# Lockbox_Schematic_V1_0.net
KiCad netlist of a schematic drawn in Altium Designer
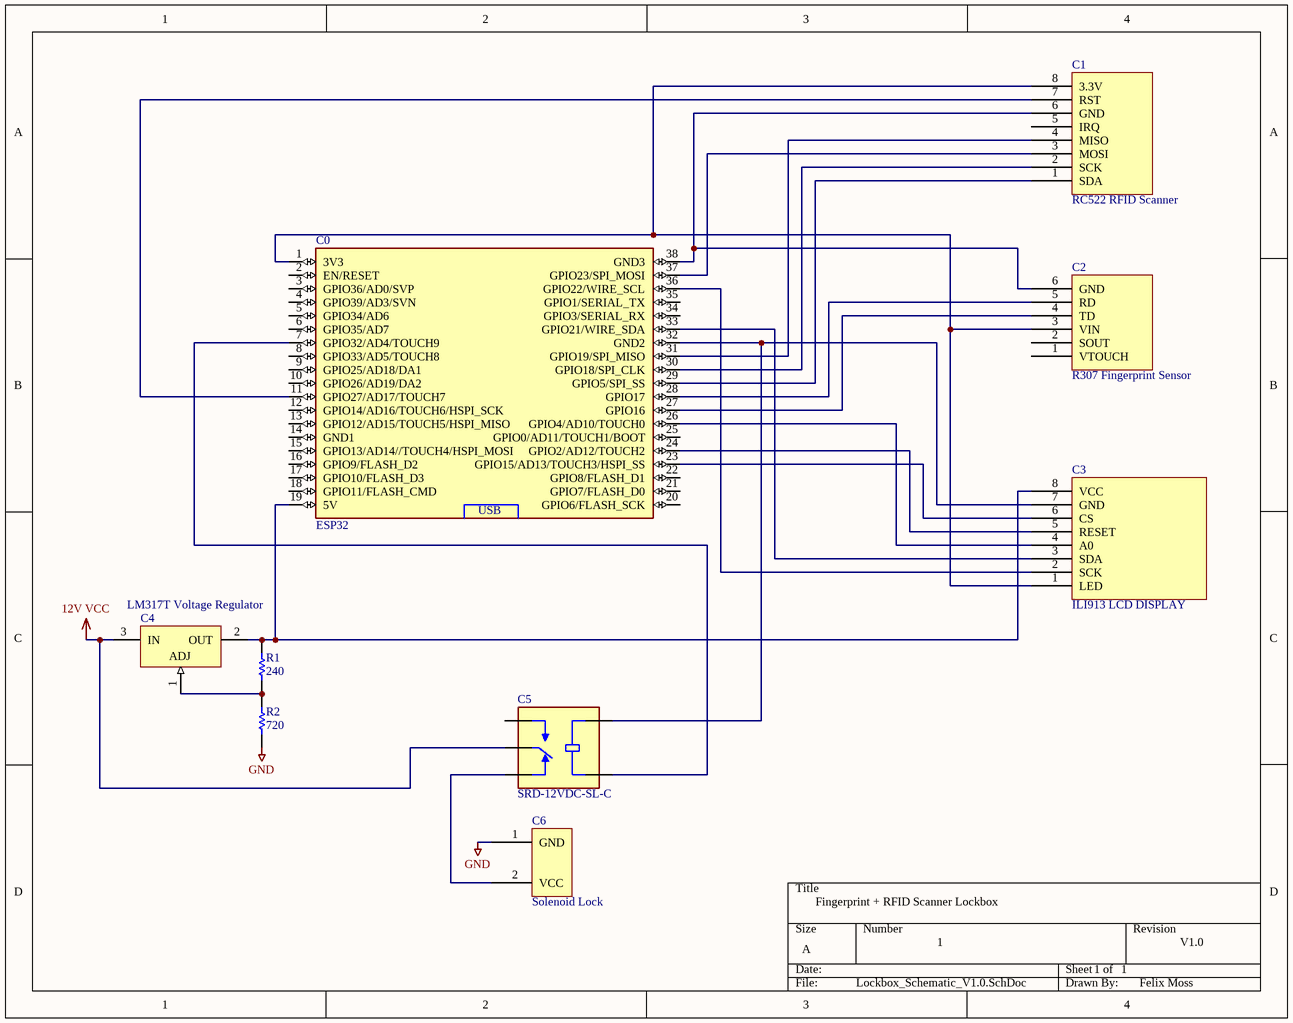
[diagram p0: Lockbox_Schematic_V1.0.SchDoc]

(export (version "E")
  (design (tool "Eeschema 10.0.6"))
  (components
    (comp (ref "C0")
      (value "ESP32")
      (footprint "ESP32-DEVKITC")
      (fields (field (name "MF") "Espressif Systems") (field (name "MP") "ESP32-DevKitC"))
      (libsource (lib "ESP32-DEVKITC") (part "ESP32-DEVKITC"))
    )
    (comp (ref "C1")
      (value "RC522 RFID Scanner")
      (description "RFID Scanner")
      (libsource (lib "Fingerprint_Mechanism_Library") (part "RFID-RC522"))
    )
    (comp (ref "C2")
      (value "R307 Fingerprint Sensor")
      (description "Fingerprint Sensor Powered by AS608")
      (libsource (lib "Fingerprint_Mechanism_Library") (part "Fingerprint Sensor"))
    )
    (comp (ref "C3")
      (value "ILI913 LCD DISPLAY")
      (description "LCD-1217")
      (libsource (lib "Fingerprint_Mechanism_Library") (part "LCD TFT DISPLAY"))
    )
    (comp (ref "C4")
      (value "LM317T Voltage Regulator")
      (footprint "TO-220")
      (description "1.5A, 1.2V to 37V Adjustable Voltage Regulator, 3-Pin TO-220")
      (libsource (lib "Altium Content Vault") (part "PM-REG-117-SIL3"))
    )
    (comp (ref "C5")
      (value "SRD-12VDC-SL-C")
      (footprint "RELAY_SRD-12VDC-SL-C")
      (description "General Purpose Non Latching 12VDC SPDT Through Hole Relays RoHS")
      (libsource (lib "SRD-12VDC-SL-C") (part "SRD-12VDC-SL-C"))
    )
    (comp (ref "C6")
      (value "Solenoid Lock")
      (description "12V 1.1A Solenoid Lock")
      (libsource (lib "Fingerprint_Mechanism_Library") (part "Solenoid Lock"))
    )
    (comp (ref "R1")
      (value "240")
      (description "Resistor")
      (libsource (lib "Simulation Generic Components") (part "Resistor"))
    )
    (comp (ref "R2")
      (value "720")
      (description "Resistor")
      (libsource (lib "Simulation Generic Components") (part "Resistor"))
    )
  )
  (nets
    (net (code "1") (name "12V VCC") (class "Default")
      (node (ref "C4") (pin "3") (pinfunction "IN_3") (pintype "power_in"))
      (node (ref "C5") (pin "COM") (pinfunction "COM_COM") (pintype "passive"))
    )
    (net (code "2") (name "GND") (class "Default")
      (node (ref "C6") (pin "1") (pinfunction "GND_1") (pintype "passive"))
      (node (ref "R2") (pin "1") (pinfunction "1_1") (pintype "passive"))
    )
    (net (code "3") (name "Net-(C0-3V3)") (class "Default")
      (node (ref "C0") (pin "1") (pinfunction "3V3_1") (pintype "bidirectional"))
      (node (ref "C1") (pin "8") (pinfunction "3.3V_8") (pintype "passive"))
      (node (ref "C2") (pin "3") (pinfunction "VIN_3") (pintype "passive"))
      (node (ref "C3") (pin "1") (pinfunction "LED_1") (pintype "passive"))
    )
    (net (code "4") (name "Net-(C0-5V)") (class "Default")
      (node (ref "C0") (pin "19") (pinfunction "5V_19") (pintype "bidirectional"))
      (node (ref "C3") (pin "8") (pinfunction "VCC_8") (pintype "passive"))
      (node (ref "C4") (pin "2") (pinfunction "OUT_2") (pintype "power_in"))
      (node (ref "R1") (pin "1") (pinfunction "1_1") (pintype "passive"))
    )
    (net (code "5") (name "Net-(C0-GND2)") (class "Default")
      (node (ref "C0") (pin "32") (pinfunction "GND2_32") (pintype "bidirectional"))
      (node (ref "C3") (pin "7") (pinfunction "GND_7") (pintype "passive"))
      (node (ref "C5") (pin "COIL2") (pinfunction "COIL2_COIL2") (pintype "passive"))
    )
    (net (code "6") (name "Net-(C0-GND3)") (class "Default")
      (node (ref "C0") (pin "38") (pinfunction "GND3_38") (pintype "bidirectional"))
      (node (ref "C1") (pin "6") (pinfunction "GND_6") (pintype "passive"))
      (node (ref "C2") (pin "6") (pinfunction "GND_6") (pintype "passive"))
    )
    (net (code "7") (name "Net-(C0-GPIO2{slash}AD12{slash}TOUCH2)") (class "Default")
      (node (ref "C0") (pin "24") (pinfunction "GPIO2/AD12/TOUCH2_24") (pintype "bidirectional"))
      (node (ref "C3") (pin "5") (pinfunction "RESET_5") (pintype "passive"))
    )
    (net (code "8") (name "Net-(C0-GPIO4{slash}AD10{slash}TOUCH0)") (class "Default")
      (node (ref "C0") (pin "26") (pinfunction "GPIO4/AD10/TOUCH0_26") (pintype "bidirectional"))
      (node (ref "C3") (pin "4") (pinfunction "A0_4") (pintype "passive"))
    )
    (net (code "9") (name "Net-(C0-GPIO5{slash}SPI_SS)") (class "Default")
      (node (ref "C0") (pin "29") (pinfunction "GPIO5/SPI_SS_29") (pintype "bidirectional"))
      (node (ref "C1") (pin "1") (pinfunction "SDA_1") (pintype "passive"))
    )
    (net (code "10") (name "Net-(C0-GPIO15{slash}AD13{slash}TOUCH3{slash}HSPI_SS)") (class "Default")
      (node (ref "C0") (pin "23") (pinfunction "GPIO15/AD13/TOUCH3/HSPI_SS_23") (pintype "bidirectional"))
      (node (ref "C3") (pin "6") (pinfunction "CS_6") (pintype "passive"))
    )
    (net (code "11") (name "Net-(C0-GPIO16)") (class "Default")
      (node (ref "C0") (pin "27") (pinfunction "GPIO16_27") (pintype "bidirectional"))
      (node (ref "C2") (pin "4") (pinfunction "TD_4") (pintype "passive"))
    )
    (net (code "12") (name "Net-(C0-GPIO17)") (class "Default")
      (node (ref "C0") (pin "28") (pinfunction "GPIO17_28") (pintype "bidirectional"))
      (node (ref "C2") (pin "5") (pinfunction "RD_5") (pintype "passive"))
    )
    (net (code "13") (name "Net-(C0-GPIO18{slash}SPI_CLK)") (class "Default")
      (node (ref "C0") (pin "30") (pinfunction "GPIO18/SPI_CLK_30") (pintype "bidirectional"))
      (node (ref "C1") (pin "2") (pinfunction "SCK_2") (pintype "passive"))
    )
    (net (code "14") (name "Net-(C0-GPIO19{slash}SPI_MISO)") (class "Default")
      (node (ref "C0") (pin "31") (pinfunction "GPIO19/SPI_MISO_31") (pintype "bidirectional"))
      (node (ref "C1") (pin "4") (pinfunction "MISO_4") (pintype "passive"))
    )
    (net (code "15") (name "Net-(C0-GPIO21{slash}WIRE_SDA)") (class "Default")
      (node (ref "C0") (pin "33") (pinfunction "GPIO21/WIRE_SDA_33") (pintype "bidirectional"))
      (node (ref "C3") (pin "3") (pinfunction "SDA_3") (pintype "passive"))
    )
    (net (code "16") (name "Net-(C0-GPIO22{slash}WIRE_SCL)") (class "Default")
      (node (ref "C0") (pin "36") (pinfunction "GPIO22/WIRE_SCL_36") (pintype "bidirectional"))
      (node (ref "C3") (pin "2") (pinfunction "SCK_2") (pintype "passive"))
    )
    (net (code "17") (name "Net-(C0-GPIO23{slash}SPI_MOSI)") (class "Default")
      (node (ref "C0") (pin "37") (pinfunction "GPIO23/SPI_MOSI_37") (pintype "bidirectional"))
      (node (ref "C1") (pin "3") (pinfunction "MOSI_3") (pintype "passive"))
    )
    (net (code "18") (name "Net-(C0-GPIO27{slash}AD17{slash}TOUCH7)") (class "Default")
      (node (ref "C0") (pin "11") (pinfunction "GPIO27/AD17/TOUCH7_11") (pintype "bidirectional"))
      (node (ref "C1") (pin "7") (pinfunction "RST_7") (pintype "passive"))
    )
    (net (code "19") (name "Net-(C0-GPIO32{slash}AD4{slash}TOUCH9)") (class "Default")
      (node (ref "C0") (pin "7") (pinfunction "GPIO32/AD4/TOUCH9_7") (pintype "bidirectional"))
      (node (ref "C5") (pin "COIL1") (pinfunction "COIL1_COIL1") (pintype "passive"))
    )
    (net (code "20") (name "Net-(C4-ADJ)") (class "Default")
      (node (ref "C4") (pin "1") (pinfunction "ADJ_1") (pintype "input"))
      (node (ref "R1") (pin "2") (pinfunction "2_2") (pintype "passive"))
      (node (ref "R2") (pin "2") (pinfunction "2_2") (pintype "passive"))
    )
    (net (code "21") (name "Net-(C6-VCC)") (class "Default")
      (node (ref "C5") (pin "NC") (pinfunction "NC_NC") (pintype "passive"))
      (node (ref "C6") (pin "2") (pinfunction "VCC_2") (pintype "passive"))
    )
    (net (code "22") (name "unconnected-(C0-EN{slash}RESET-Pad2)") (class "Default")
      (node (ref "C0") (pin "2") (pinfunction "EN/RESET_2") (pintype "bidirectional"))
    )
    (net (code "23") (name "unconnected-(C0-GND1-Pad14)") (class "Default")
      (node (ref "C0") (pin "14") (pinfunction "GND1_14") (pintype "bidirectional"))
    )
    (net (code "24") (name "unconnected-(C0-GPIO0{slash}AD11{slash}TOUCH1{slash}BOOT-Pad25)") (class "Default")
      (node (ref "C0") (pin "25") (pinfunction "GPIO0/AD11/TOUCH1/BOOT_25") (pintype "bidirectional"))
    )
    (net (code "25") (name "unconnected-(C0-GPIO1{slash}SERIAL_TX-Pad35)") (class "Default")
      (node (ref "C0") (pin "35") (pinfunction "GPIO1/SERIAL_TX_35") (pintype "bidirectional"))
    )
    (net (code "26") (name "unconnected-(C0-GPIO3{slash}SERIAL_RX-Pad34)") (class "Default")
      (node (ref "C0") (pin "34") (pinfunction "GPIO3/SERIAL_RX_34") (pintype "bidirectional"))
    )
    (net (code "27") (name "unconnected-(C0-GPIO6{slash}FLASH_SCK-Pad20)") (class "Default")
      (node (ref "C0") (pin "20") (pinfunction "GPIO6/FLASH_SCK_20") (pintype "bidirectional"))
    )
    (net (code "28") (name "unconnected-(C0-GPIO7{slash}FLASH_D0-Pad21)") (class "Default")
      (node (ref "C0") (pin "21") (pinfunction "GPIO7/FLASH_D0_21") (pintype "bidirectional"))
    )
    (net (code "29") (name "unconnected-(C0-GPIO8{slash}FLASH_D1-Pad22)") (class "Default")
      (node (ref "C0") (pin "22") (pinfunction "GPIO8/FLASH_D1_22") (pintype "bidirectional"))
    )
    (net (code "30") (name "unconnected-(C0-GPIO9{slash}FLASH_D2-Pad16)") (class "Default")
      (node (ref "C0") (pin "16") (pinfunction "GPIO9/FLASH_D2_16") (pintype "bidirectional"))
    )
    (net (code "31") (name "unconnected-(C0-GPIO10{slash}FLASH_D3-Pad17)") (class "Default")
      (node (ref "C0") (pin "17") (pinfunction "GPIO10/FLASH_D3_17") (pintype "bidirectional"))
    )
    (net (code "32") (name "unconnected-(C0-GPIO11{slash}FLASH_CMD-Pad18)") (class "Default")
      (node (ref "C0") (pin "18") (pinfunction "GPIO11/FLASH_CMD_18") (pintype "bidirectional"))
    )
    (net (code "33") (name "unconnected-(C0-GPIO12{slash}AD15{slash}TOUCH5{slash}HSPI_MISO-Pad13)") (class "Default")
      (node (ref "C0") (pin "13") (pinfunction "GPIO12/AD15/TOUCH5/HSPI_MISO_13") (pintype "bidirectional"))
    )
    (net (code "34") (name "unconnected-(C0-GPIO13{slash}AD14{slash}{slash}TOUCH4{slash}HSPI_MOSI-Pad15)") (class "Default")
      (node (ref "C0") (pin "15") (pinfunction "GPIO13/AD14//TOUCH4/HSPI_MOSI_15") (pintype "bidirectional"))
    )
    (net (code "35") (name "unconnected-(C0-GPIO14{slash}AD16{slash}TOUCH6{slash}HSPI_SCK-Pad12)") (class "Default")
      (node (ref "C0") (pin "12") (pinfunction "GPIO14/AD16/TOUCH6/HSPI_SCK_12") (pintype "bidirectional"))
    )
    (net (code "36") (name "unconnected-(C0-GPIO25{slash}AD18{slash}DA1-Pad9)") (class "Default")
      (node (ref "C0") (pin "9") (pinfunction "GPIO25/AD18/DA1_9") (pintype "bidirectional"))
    )
    (net (code "37") (name "unconnected-(C0-GPIO26{slash}AD19{slash}DA2-Pad10)") (class "Default")
      (node (ref "C0") (pin "10") (pinfunction "GPIO26/AD19/DA2_10") (pintype "bidirectional"))
    )
    (net (code "38") (name "unconnected-(C0-GPIO33{slash}AD5{slash}TOUCH8-Pad8)") (class "Default")
      (node (ref "C0") (pin "8") (pinfunction "GPIO33/AD5/TOUCH8_8") (pintype "bidirectional"))
    )
    (net (code "39") (name "unconnected-(C0-GPIO34{slash}AD6-Pad5)") (class "Default")
      (node (ref "C0") (pin "5") (pinfunction "GPIO34/AD6_5") (pintype "bidirectional"))
    )
    (net (code "40") (name "unconnected-(C0-GPIO35{slash}AD7-Pad6)") (class "Default")
      (node (ref "C0") (pin "6") (pinfunction "GPIO35/AD7_6") (pintype "bidirectional"))
    )
    (net (code "41") (name "unconnected-(C0-GPIO36{slash}AD0{slash}SVP-Pad3)") (class "Default")
      (node (ref "C0") (pin "3") (pinfunction "GPIO36/AD0/SVP_3") (pintype "bidirectional"))
    )
    (net (code "42") (name "unconnected-(C0-GPIO39{slash}AD3{slash}SVN-Pad4)") (class "Default")
      (node (ref "C0") (pin "4") (pinfunction "GPIO39/AD3/SVN_4") (pintype "bidirectional"))
    )
    (net (code "43") (name "unconnected-(C1-IRQ-Pad5)") (class "Default")
      (node (ref "C1") (pin "5") (pinfunction "IRQ_5") (pintype "passive"))
    )
    (net (code "44") (name "unconnected-(C2-SOUT-Pad2)") (class "Default")
      (node (ref "C2") (pin "2") (pinfunction "SOUT_2") (pintype "passive"))
    )
    (net (code "45") (name "unconnected-(C2-VTOUCH-Pad1)") (class "Default")
      (node (ref "C2") (pin "1") (pinfunction "VTOUCH_1") (pintype "passive"))
    )
    (net (code "46") (name "unconnected-(C5-PadNO)") (class "Default")
      (node (ref "C5") (pin "NO") (pinfunction "NO_NO") (pintype "passive"))
    )
  )
)
